# SimPL_IMU_v1_0_DEC25.net
KiCad netlist of a schematic drawn in Altium Designer
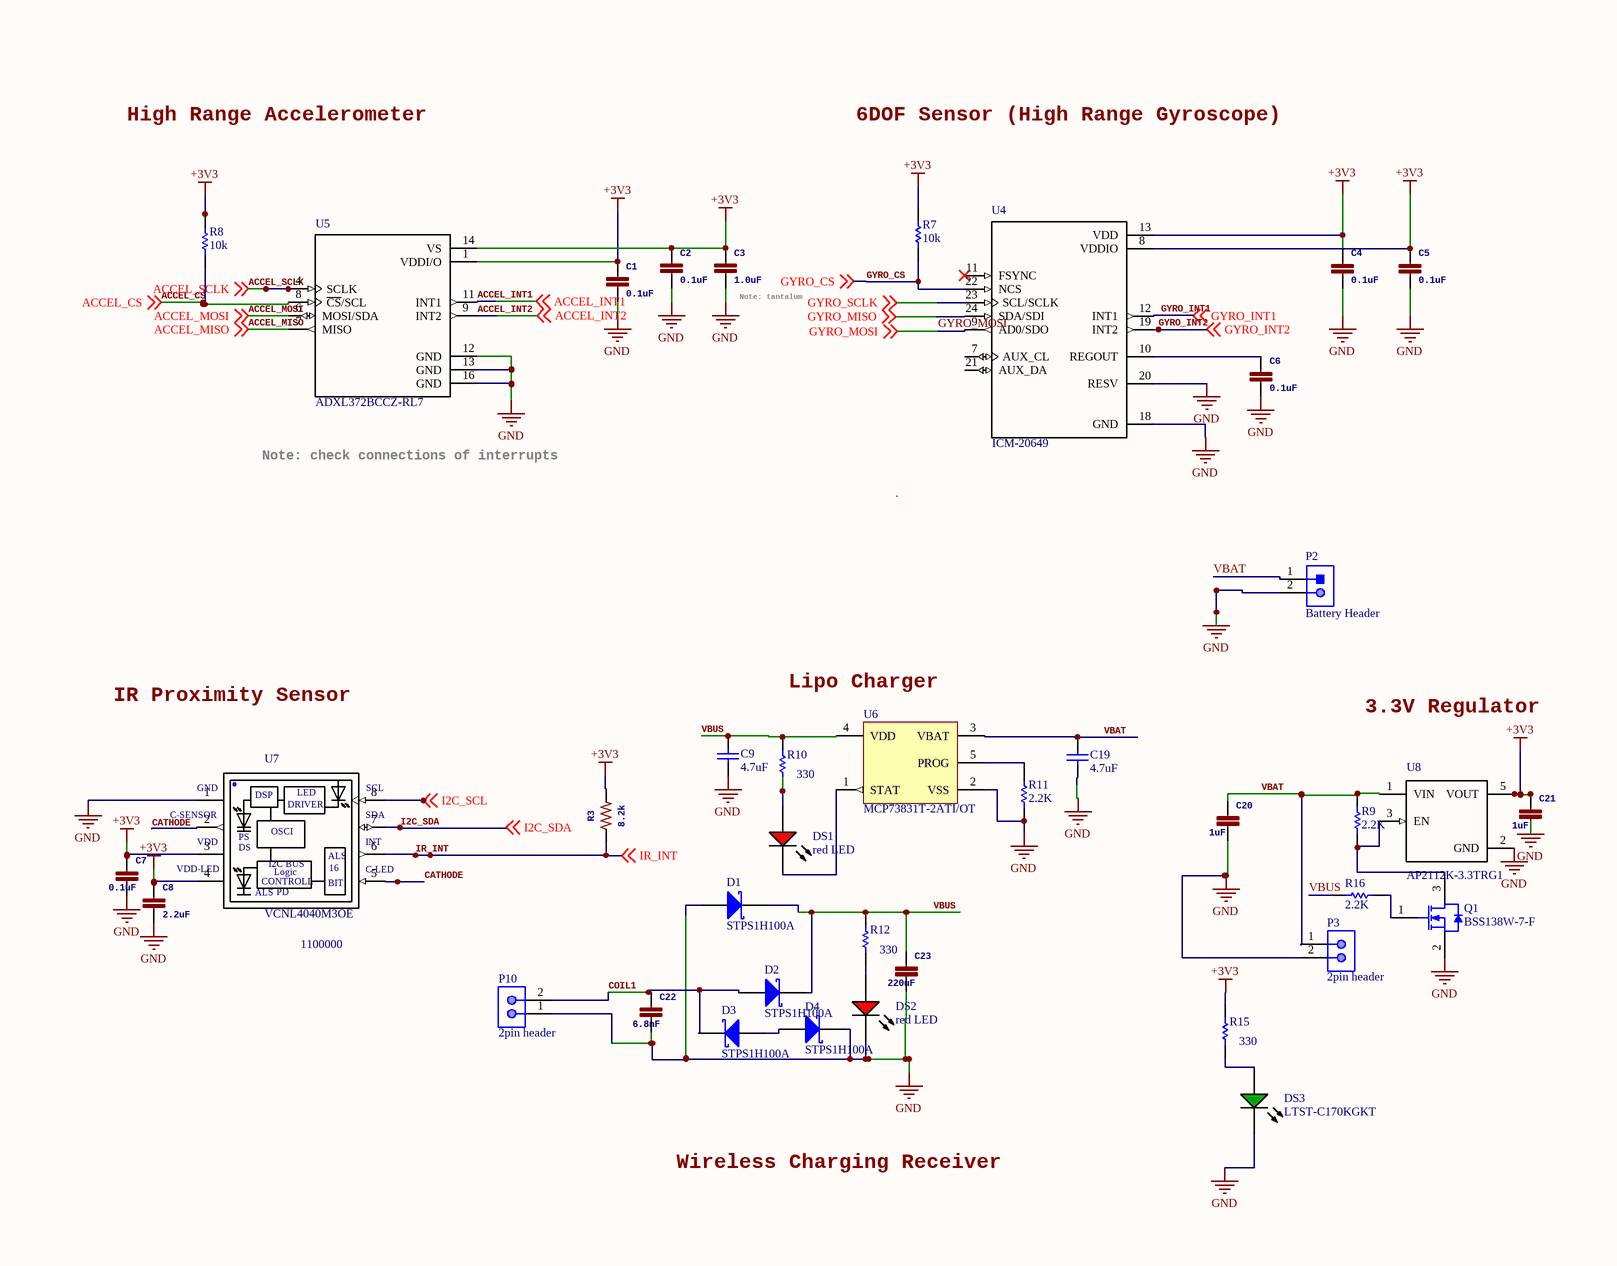
[diagram p0: SimPL_IMU_v1_0_DEC25.SchDoc]

(export (version "E")
  (design (tool "Eeschema 10.0.6"))
  (components
    (comp (ref "C1")
      (value "0.1uF")
      (footprint "0402")
      (libsource (lib "SparkFun-Capacitors") (part "0.1UF-0402-16V-10%"))
    )
    (comp (ref "C2")
      (value "0.1uF")
      (footprint "0402")
      (libsource (lib "SparkFun-Capacitors") (part "0.1UF-0402-16V-10%"))
    )
    (comp (ref "C3")
      (value "1.0uF")
      (footprint "0402")
      (libsource (lib "SparkFun-Capacitors") (part "1.0UF-0402-16V-10%"))
    )
    (comp (ref "C4")
      (value "0.1uF")
      (footprint "0402")
      (libsource (lib "SparkFun-Capacitors") (part "0.1UF-0402-16V-10%"))
    )
    (comp (ref "C5")
      (value "0.1uF")
      (footprint "0402")
      (libsource (lib "SparkFun-Capacitors") (part "0.1UF-0402-16V-10%"))
    )
    (comp (ref "C6")
      (value "0.1uF")
      (footprint "0402")
      (libsource (lib "SparkFun-Capacitors") (part "0.1UF-0402-16V-10%"))
    )
    (comp (ref "C7")
      (value "0.1uF")
      (footprint "0402")
      (libsource (lib "SparkFun-Capacitors") (part "0.1UF-0402-16V-10%"))
    )
    (comp (ref "C8")
      (value "2.2uF")
      (footprint "0402")
      (libsource (lib "SparkFun-Capacitors") (part "0.1UF-0402-16V-10%"))
    )
    (comp (ref "C9")
      (value "4.7uF")
      (footprint "CAPC1005X65X10ML15")
      (description "Chip Capacitor, 4.7 uF, +/- 20%, 10 V, -55 to 85 degC, 0402 (1005 Metric), RoHS, Tape and Reel")
      (fields
        (field (name "TOLERANCE") "±20%")
        (field (name "PCN PART NUMBER") "MLCCPartNumberChange30/Nov/2012")
      )
      (libsource (lib "Altium Content Vault") (part "CAP-NP-2"))
    )
    (comp (ref "C19")
      (value "4.7uF")
      (footprint "CAPC1005X65X10ML15")
      (description "Chip Capacitor, 4.7 uF, +/- 20%, 10 V, -55 to 85 degC, 0402 (1005 Metric), RoHS, Tape and Reel")
      (fields
        (field (name "TOLERANCE") "±20%")
        (field (name "PCN PART NUMBER") "MLCCPartNumberChange30/Nov/2012")
      )
      (libsource (lib "Altium Content Vault") (part "CAP-NP-2"))
    )
    (comp (ref "C20")
      (value "1uF")
      (footprint "0402")
      (libsource (lib "SparkFun-Capacitors") (part "0.1UF-0402-16V-10%"))
    )
    (comp (ref "C21")
      (value "1uF")
      (footprint "0402")
      (libsource (lib "SparkFun-Capacitors") (part "0.1UF-0402-16V-10%"))
    )
    (comp (ref "C22")
      (value "6.8nF")
      (footprint "0402")
      (libsource (lib "SparkFun-Capacitors") (part "0.1UF-0402-16V-10%"))
    )
    (comp (ref "C23")
      (value "220uF")
      (footprint "0402")
      (libsource (lib "SparkFun-Capacitors") (part "0.1UF-0402-16V-10%"))
    )
    (comp (ref "D1")
      (value "STPS1H100A")
      (footprint "STM-SMA-2_V")
      (description "High Voltage Power Schottky Rectifier, 1 A, 100 V, 2-Pin SMD (SMA), RoHS, Tape and Reel")
      (fields (field (name "MANUFACTURER") "STMicroelectronics"))
      (libsource (lib "Altium Content Vault") (part "DSKY-AK-2"))
    )
    (comp (ref "D2")
      (value "STPS1H100A")
      (footprint "STM-SMA-2_V")
      (description "High Voltage Power Schottky Rectifier, 1 A, 100 V, 2-Pin SMD (SMA), RoHS, Tape and Reel")
      (fields (field (name "MANUFACTURER") "STMicroelectronics"))
      (libsource (lib "Altium Content Vault") (part "DSKY-AK-2"))
    )
    (comp (ref "D3")
      (value "STPS1H100A")
      (footprint "STM-SMA-2_V")
      (description "High Voltage Power Schottky Rectifier, 1 A, 100 V, 2-Pin SMD (SMA), RoHS, Tape and Reel")
      (fields (field (name "MANUFACTURER") "STMicroelectronics"))
      (libsource (lib "Altium Content Vault") (part "DSKY-AK-2"))
    )
    (comp (ref "D4")
      (value "STPS1H100A")
      (footprint "STM-SMA-2_V")
      (description "High Voltage Power Schottky Rectifier, 1 A, 100 V, 2-Pin SMD (SMA), RoHS, Tape and Reel")
      (fields (field (name "MANUFACTURER") "STMicroelectronics"))
      (libsource (lib "Altium Content Vault") (part "DSKY-AK-2"))
    )
    (comp (ref "DS1")
      (value "red LED")
      (footprint "VISH-TLMS1000_V")
      (description "Low Current LED, 40 mW, 1.8 V, -40 to 100 degC, 2-Pin SMD (0603), RoHS, Tape and Reel")
      (fields (field (name "MANUFACTURER") "Vishay"))
      (libsource (lib "Altium Content Vault") (part "LED-RED-AK-2"))
    )
    (comp (ref "DS2")
      (value "red LED")
      (footprint "VISH-TLMS1000_V")
      (description "Low Current LED, 40 mW, 1.8 V, -40 to 100 degC, 2-Pin SMD (0603), RoHS, Tape and Reel")
      (fields (field (name "MANUFACTURER") "Vishay"))
      (libsource (lib "Altium Content Vault") (part "LED-RED-AK-2"))
    )
    (comp (ref "DS3")
      (value "LTST-C170KGKT")
      (footprint "LTST-LTST-C170KGKT-2_V")
      (description "Ultra Bright AlInGaP Chip LED, 75 mW, -55 to 85 degC, 2-Pin SMD (0805), RoHS, Tape and Reel")
      (fields (field (name "MANUFACTURER") "Lite-On"))
      (libsource (lib "Altium Content Vault") (part "LED-GREEN-KA-2"))
    )
    (comp (ref "P2")
      (value "Battery Header")
      (footprint "JST-S2B-PH-K-S_V")
      (fields (field (name "TOLERANCE") "20%"))
      (libsource (lib "") (part "CN-1P-M-R2_1"))
    )
    (comp (ref "P3")
      (value "2pin header")
      (footprint "AMPH-68000-102HLF_V")
      (description "Male Header, Pitch 2.54 mm, 1 x 2 Position, Height 8.38 mm, Tail Length 2.41 mm, RoHS, Bulk")
      (fields (field (name "MANUFACTURER") "FCI"))
      (libsource (lib "Altium Content Vault") (part "CN-1P-M-R2"))
    )
    (comp (ref "P10")
      (value "2pin header")
      (footprint "AMPH-68000-102HLF_V")
      (description "Male Header, Pitch 2.54 mm, 1 x 2 Position, Height 8.38 mm, Tail Length 2.41 mm, RoHS, Bulk")
      (fields (field (name "MANUFACTURER") "FCI"))
      (libsource (lib "") (part "CN-1P-M-R2_2"))
    )
    (comp (ref "Q1")
      (value "BSS138W-7-F")
      (footprint "DIOD-SOT323-3_V")
      (fields (field (name "MANUFACTURER") "DiodesIncorporated"))
      (libsource (lib "Altium Content Vault") (part "NEMOS-GSD-3"))
    )
    (comp (ref "R3")
      (value "8.2k")
      (footprint "0603")
      (libsource (lib "SparkFun-Resistors") (part "8.2KOHM-0603-1/10W-5%"))
    )
    (comp (ref "R7")
      (value "10k")
      (footprint "RESC1005X40X25NL05T05")
      (description "Chip Resistor, 10 KOhm, +/- 1%, 100 mW, -55 to 155 degC, 0402 (1005 Metric), RoHS, Tape and Reel")
      (fields (field (name "MANUFACTURER") "Basic Passives") (field (name "TOLERANCE") "1%"))
      (libsource (lib "Altium Content Vault") (part "RES-2"))
    )
    (comp (ref "R8")
      (value "10k")
      (footprint "RESC1005X40X25NL05T05")
      (description "Chip Resistor, 10 KOhm, +/- 1%, 100 mW, -55 to 155 degC, 0402 (1005 Metric), RoHS, Tape and Reel")
      (fields (field (name "MANUFACTURER") "Basic Passives") (field (name "TOLERANCE") "1%"))
      (libsource (lib "Altium Content Vault") (part "RES-2"))
    )
    (comp (ref "R9")
      (value "2.2K")
      (footprint "RESC1005X40X25ML10T10")
      (fields (field (name "PART NUMBER") "MC00625W040212K2") (field (name "MANUFACTURER") "Multicomp"))
      (libsource (lib "Altium Content Vault") (part "RES"))
    )
    (comp (ref "R10")
      (value "330")
      (footprint "RESC2013X50X30NL20T20")
      (fields (field (name "MANUFACTURER") "Vishay Dale") (field (name "PART NUMBER") "CRCW0805330RFKEA"))
      (libsource (lib "Altium Content Vault") (part "RES"))
    )
    (comp (ref "R11")
      (value "2.2K")
      (footprint "RESC1005X40X25ML10T10")
      (fields (field (name "PART NUMBER") "MC00625W040212K2") (field (name "MANUFACTURER") "Multicomp"))
      (libsource (lib "Altium Content Vault") (part "RES"))
    )
    (comp (ref "R12")
      (value "330")
      (footprint "RESC2013X50X30NL20T20")
      (fields (field (name "MANUFACTURER") "Vishay Dale") (field (name "PART NUMBER") "CRCW0805330RFKEA"))
      (libsource (lib "Altium Content Vault") (part "RES"))
    )
    (comp (ref "R15")
      (value "330")
      (footprint "RESC2013X50X30NL20T20")
      (fields (field (name "MANUFACTURER") "Vishay Dale") (field (name "PART NUMBER") "CRCW0805330RFKEA"))
      (libsource (lib "Altium Content Vault") (part "RES"))
    )
    (comp (ref "R16")
      (value "2.2K")
      (footprint "RESC1005X40X25ML10T10")
      (fields (field (name "PART NUMBER") "MC00625W040212K2") (field (name "MANUFACTURER") "Multicomp"))
      (libsource (lib "Altium Content Vault") (part "RES"))
    )
    (comp (ref "U4")
      (value "ICM-20649")
      (footprint "*QFN40P300X300X95-24N")
      (description "Wide-Range 6-Axis MEMS MotionTracking Device for Sports and High Impact Applications")
      (fields (field (name "MF") "TDK InvenSense"))
      (libsource (lib "ICM-20649") (part "ICM-20649"))
    )
    (comp (ref "U5")
      (value "ADXL372BCCZ-RL7")
      (footprint "*PQFN50P322X300X114-16N")
      (description "Accelerometer Triple Â±200g 2.5V 16-Pin LGA T/R")
      (fields (field (name "MF") "Analog Devices"))
      (libsource (lib "ADXL372BCCZ-RL7") (part "ADXL372BCCZ-RL7"))
    )
    (comp (ref "U6")
      (value "MCP73831T-2ATI/OT")
      (footprint "SOT-23-OT5_M")
      (libsource (lib "Altium Content Vault") (part "PM-BM-MCP73831-SOT5"))
    )
    (comp (ref "U7")
      (value "VCNL4040M3OE")
      (footprint "*VISHAY_VCNL4040_4X2X1.1")
      (description "VCNL4040 Series 3.6 V 200 mm 16 Bit I2C SMT Proximity and Ambient Light Sensor")
      (fields (field (name "MF") "Vishay"))
      (libsource (lib "VCNL4040M3OE") (part "VCNL4040M3OE"))
    )
    (comp (ref "U8")
      (value "AP2112K-3.3TRG1")
      (footprint "*SOT95P285X140-5N")
      (description "AP2112 Series 0.6 A 3.3 V Fixed Output SMT LDO Linear Regulator - SOT23-5")
      (fields (field (name "MF") "Diodes Inc."))
      (libsource (lib "AP2112K-3.3TRG1") (part "AP2112K-3.3TRG1"))
    )
  )
  (nets
    (net (code "1") (name "+3V3") (class "Default")
      (node (ref "C1") (pin "1") (pinfunction "1_1") (pintype "passive"))
      (node (ref "C2") (pin "1") (pinfunction "1_1") (pintype "passive"))
      (node (ref "C21") (pin "1") (pinfunction "1_1") (pintype "passive"))
      (node (ref "C3") (pin "1") (pinfunction "1_1") (pintype "passive"))
      (node (ref "C4") (pin "1") (pinfunction "1_1") (pintype "passive"))
      (node (ref "C5") (pin "1") (pinfunction "1_1") (pintype "passive"))
      (node (ref "C7") (pin "1") (pinfunction "1_1") (pintype "passive"))
      (node (ref "C8") (pin "1") (pinfunction "1_1") (pintype "passive"))
      (node (ref "R15") (pin "2") (pinfunction "2_2") (pintype "passive"))
      (node (ref "R3") (pin "2") (pinfunction "2_2") (pintype "passive"))
      (node (ref "R7") (pin "2") (pinfunction "2_2") (pintype "passive"))
      (node (ref "R8") (pin "2") (pinfunction "2_2") (pintype "passive"))
      (node (ref "U4") (pin "13") (pinfunction "VDD_13") (pintype "power_in"))
      (node (ref "U4") (pin "8") (pinfunction "VDDIO_8") (pintype "power_in"))
      (node (ref "U5") (pin "1") (pinfunction "VDDI/O_1") (pintype "power_in"))
      (node (ref "U5") (pin "14") (pinfunction "VS_14") (pintype "power_in"))
      (node (ref "U7") (pin "3") (pinfunction "VDD_3") (pintype "power_in"))
      (node (ref "U7") (pin "4") (pinfunction "VDD-LED_4") (pintype "power_in"))
      (node (ref "U8") (pin "5") (pinfunction "VOUT_5") (pintype "power_in"))
    )
    (net (code "2") (name "/CATHODE") (class "Default")
      (node (ref "U7") (pin "2") (pinfunction "C-SENSOR_2") (pintype "output"))
      (node (ref "U7") (pin "5") (pinfunction "C-LED_5") (pintype "input"))
    )
    (net (code "3") (name "/COIL1") (class "Default")
      (node (ref "C22") (pin "1") (pinfunction "1_1") (pintype "passive"))
      (node (ref "D2") (pin "1") (pinfunction "A_1") (pintype "passive"))
      (node (ref "D3") (pin "2") (pinfunction "K_2") (pintype "passive"))
      (node (ref "P10") (pin "2") (pinfunction "2_2") (pintype "passive"))
    )
    (net (code "4") (name "/VBAT") (class "Default")
      (node (ref "C19") (pin "2") (pinfunction "2_2") (pintype "passive"))
      (node (ref "C20") (pin "1") (pinfunction "1_1") (pintype "passive"))
      (node (ref "P2") (pin "1") (pinfunction "1_1") (pintype "passive"))
      (node (ref "P3") (pin "1") (pinfunction "1_1") (pintype "passive"))
      (node (ref "R9") (pin "2") (pinfunction "2_2") (pintype "passive"))
      (node (ref "U6") (pin "3") (pinfunction "VBAT_3") (pintype "power_in"))
      (node (ref "U8") (pin "1") (pinfunction "VIN_1") (pintype "power_in"))
    )
    (net (code "5") (name "/VBUS") (class "Default")
      (node (ref "C23") (pin "1") (pinfunction "1_1") (pintype "passive"))
      (node (ref "C9") (pin "2") (pinfunction "2_2") (pintype "passive"))
      (node (ref "D1") (pin "2") (pinfunction "K_2") (pintype "passive"))
      (node (ref "D2") (pin "2") (pinfunction "K_2") (pintype "passive"))
      (node (ref "R10") (pin "2") (pinfunction "2_2") (pintype "passive"))
      (node (ref "R12") (pin "2") (pinfunction "2_2") (pintype "passive"))
      (node (ref "R16") (pin "2") (pinfunction "2_2") (pintype "passive"))
      (node (ref "U6") (pin "4") (pinfunction "VDD_4") (pintype "power_in"))
    )
    (net (code "6") (name "ACCEL_CS") (class "Default")
      (node (ref "R8") (pin "1") (pinfunction "1_1") (pintype "passive"))
      (node (ref "U5") (pin "8") (pinfunction "~{CS}/SCL_8") (pintype "input"))
    )
    (net (code "7") (name "ACCEL_INT1") (class "Default")
      (node (ref "U5") (pin "11") (pinfunction "INT1_11") (pintype "output"))
    )
    (net (code "8") (name "ACCEL_INT2") (class "Default")
      (node (ref "U5") (pin "9") (pinfunction "INT2_9") (pintype "output"))
    )
    (net (code "9") (name "ACCEL_MISO") (class "Default")
      (node (ref "U5") (pin "7") (pinfunction "MISO_7") (pintype "output"))
    )
    (net (code "10") (name "ACCEL_MOSI") (class "Default")
      (node (ref "U5") (pin "6") (pinfunction "MOSI/SDA_6") (pintype "bidirectional"))
    )
    (net (code "11") (name "ACCEL_SCLK") (class "Default")
      (node (ref "U5") (pin "4") (pinfunction "SCLK_4") (pintype "input"))
    )
    (net (code "12") (name "GND") (class "Default")
      (node (ref "C1") (pin "2") (pinfunction "2_2") (pintype "passive"))
      (node (ref "C19") (pin "1") (pinfunction "1_1") (pintype "passive"))
      (node (ref "C2") (pin "2") (pinfunction "2_2") (pintype "passive"))
      (node (ref "C20") (pin "2") (pinfunction "2_2") (pintype "passive"))
      (node (ref "C21") (pin "2") (pinfunction "2_2") (pintype "passive"))
      (node (ref "C22") (pin "2") (pinfunction "2_2") (pintype "passive"))
      (node (ref "C23") (pin "2") (pinfunction "2_2") (pintype "passive"))
      (node (ref "C3") (pin "2") (pinfunction "2_2") (pintype "passive"))
      (node (ref "C4") (pin "2") (pinfunction "2_2") (pintype "passive"))
      (node (ref "C5") (pin "2") (pinfunction "2_2") (pintype "passive"))
      (node (ref "C6") (pin "2") (pinfunction "2_2") (pintype "passive"))
      (node (ref "C7") (pin "2") (pinfunction "2_2") (pintype "passive"))
      (node (ref "C8") (pin "2") (pinfunction "2_2") (pintype "passive"))
      (node (ref "C9") (pin "1") (pinfunction "1_1") (pintype "passive"))
      (node (ref "D1") (pin "1") (pinfunction "A_1") (pintype "passive"))
      (node (ref "D4") (pin "2") (pinfunction "K_2") (pintype "passive"))
      (node (ref "DS2") (pin "2") (pinfunction "K_2") (pintype "passive"))
      (node (ref "DS3") (pin "1") (pinfunction "K_1") (pintype "passive"))
      (node (ref "P10") (pin "1") (pinfunction "1_1") (pintype "passive"))
      (node (ref "P2") (pin "2") (pinfunction "2_2") (pintype "passive"))
      (node (ref "P3") (pin "2") (pinfunction "2_2") (pintype "passive"))
      (node (ref "Q1") (pin "2") (pinfunction "S_2") (pintype "passive"))
      (node (ref "R11") (pin "1") (pinfunction "1_1") (pintype "passive"))
      (node (ref "U4") (pin "18") (pinfunction "GND_18") (pintype "power_in"))
      (node (ref "U4") (pin "20") (pinfunction "RESV_20") (pintype "passive"))
      (node (ref "U5") (pin "12") (pinfunction "GND_12") (pintype "power_in"))
      (node (ref "U5") (pin "13") (pinfunction "GND_13") (pintype "power_in"))
      (node (ref "U5") (pin "16") (pinfunction "GND_16") (pintype "power_in"))
      (node (ref "U6") (pin "2") (pinfunction "VSS_2") (pintype "power_in"))
      (node (ref "U7") (pin "1") (pinfunction "GND_1") (pintype "power_in"))
      (node (ref "U8") (pin "2") (pinfunction "GND_2") (pintype "power_in"))
    )
    (net (code "13") (name "GYRO_CS") (class "Default")
      (node (ref "R7") (pin "1") (pinfunction "1_1") (pintype "passive"))
      (node (ref "U4") (pin "22") (pinfunction "NCS_22") (pintype "input"))
    )
    (net (code "14") (name "GYRO_INT1") (class "Default")
      (node (ref "U4") (pin "12") (pinfunction "INT1_12") (pintype "output"))
    )
    (net (code "15") (name "GYRO_INT2") (class "Default")
      (node (ref "U4") (pin "19") (pinfunction "INT2_19") (pintype "output"))
    )
    (net (code "16") (name "GYRO_MISO") (class "Default")
      (node (ref "U4") (pin "24") (pinfunction "SDA/SDI_24") (pintype "input"))
    )
    (net (code "17") (name "GYRO_MOSI") (class "Default")
      (node (ref "U4") (pin "9") (pinfunction "AD0/SDO_9") (pintype "output"))
    )
    (net (code "18") (name "GYRO_SCLK") (class "Default")
      (node (ref "U4") (pin "23") (pinfunction "SCL/SCLK_23") (pintype "input"))
    )
    (net (code "19") (name "I2C_SCL") (class "Default")
      (node (ref "U7") (pin "8") (pinfunction "SCL_8") (pintype "input"))
    )
    (net (code "20") (name "I2C_SDA") (class "Default")
      (node (ref "U7") (pin "7") (pinfunction "SDA_7") (pintype "bidirectional"))
    )
    (net (code "21") (name "IR_INT") (class "Default")
      (node (ref "R3") (pin "1") (pinfunction "1_1") (pintype "passive"))
      (node (ref "U7") (pin "6") (pinfunction "INT_6") (pintype "output"))
    )
    (net (code "22") (name "Net-(D3-A)") (class "Default")
      (node (ref "D3") (pin "1") (pinfunction "A_1") (pintype "passive"))
      (node (ref "D4") (pin "1") (pinfunction "A_1") (pintype "passive"))
    )
    (net (code "23") (name "Net-(DS1-A)") (class "Default")
      (node (ref "DS1") (pin "1") (pinfunction "A_1") (pintype "passive"))
      (node (ref "R10") (pin "1") (pinfunction "1_1") (pintype "passive"))
    )
    (net (code "24") (name "Net-(DS1-K)") (class "Default")
      (node (ref "DS1") (pin "2") (pinfunction "K_2") (pintype "passive"))
      (node (ref "U6") (pin "1") (pinfunction "STAT_1") (pintype "output"))
    )
    (net (code "25") (name "Net-(DS2-A)") (class "Default")
      (node (ref "DS2") (pin "1") (pinfunction "A_1") (pintype "passive"))
      (node (ref "R12") (pin "1") (pinfunction "1_1") (pintype "passive"))
    )
    (net (code "26") (name "Net-(DS3-A)") (class "Default")
      (node (ref "DS3") (pin "2") (pinfunction "A_2") (pintype "passive"))
      (node (ref "R15") (pin "1") (pinfunction "1_1") (pintype "passive"))
    )
    (net (code "27") (name "Net-(Q1-D)") (class "Default")
      (node (ref "Q1") (pin "3") (pinfunction "D_3") (pintype "passive"))
      (node (ref "R9") (pin "1") (pinfunction "1_1") (pintype "passive"))
      (node (ref "U8") (pin "3") (pinfunction "EN_3") (pintype "input"))
    )
    (net (code "28") (name "Net-(Q1-G)") (class "Default")
      (node (ref "Q1") (pin "1") (pinfunction "G_1") (pintype "passive"))
      (node (ref "R16") (pin "1") (pinfunction "1_1") (pintype "passive"))
    )
    (net (code "29") (name "Net-(U4-REGOUT)") (class "Default")
      (node (ref "C6") (pin "1") (pinfunction "1_1") (pintype "passive"))
      (node (ref "U4") (pin "10") (pinfunction "REGOUT_10") (pintype "passive"))
    )
    (net (code "30") (name "Net-(U6-PROG)") (class "Default")
      (node (ref "R11") (pin "2") (pinfunction "2_2") (pintype "passive"))
      (node (ref "U6") (pin "5") (pinfunction "PROG_5") (pintype "passive"))
    )
    (net (code "31") (name "unconnected-(U4-AUX_CL-Pad7)") (class "Default")
      (node (ref "U4") (pin "7") (pinfunction "AUX_CL_7") (pintype "bidirectional"))
    )
    (net (code "32") (name "unconnected-(U4-AUX_DA-Pad21)") (class "Default")
      (node (ref "U4") (pin "21") (pinfunction "AUX_DA_21") (pintype "bidirectional"))
    )
    (net (code "33") (name "unconnected-(U4-FSYNC-Pad11)") (class "Default")
      (node (ref "U4") (pin "11") (pinfunction "FSYNC_11") (pintype "input+no_connect"))
    )
  )
)
